# Nixie_HV_PSU_MAX1771.net
KiCad netlist of a schematic drawn in EAGLE
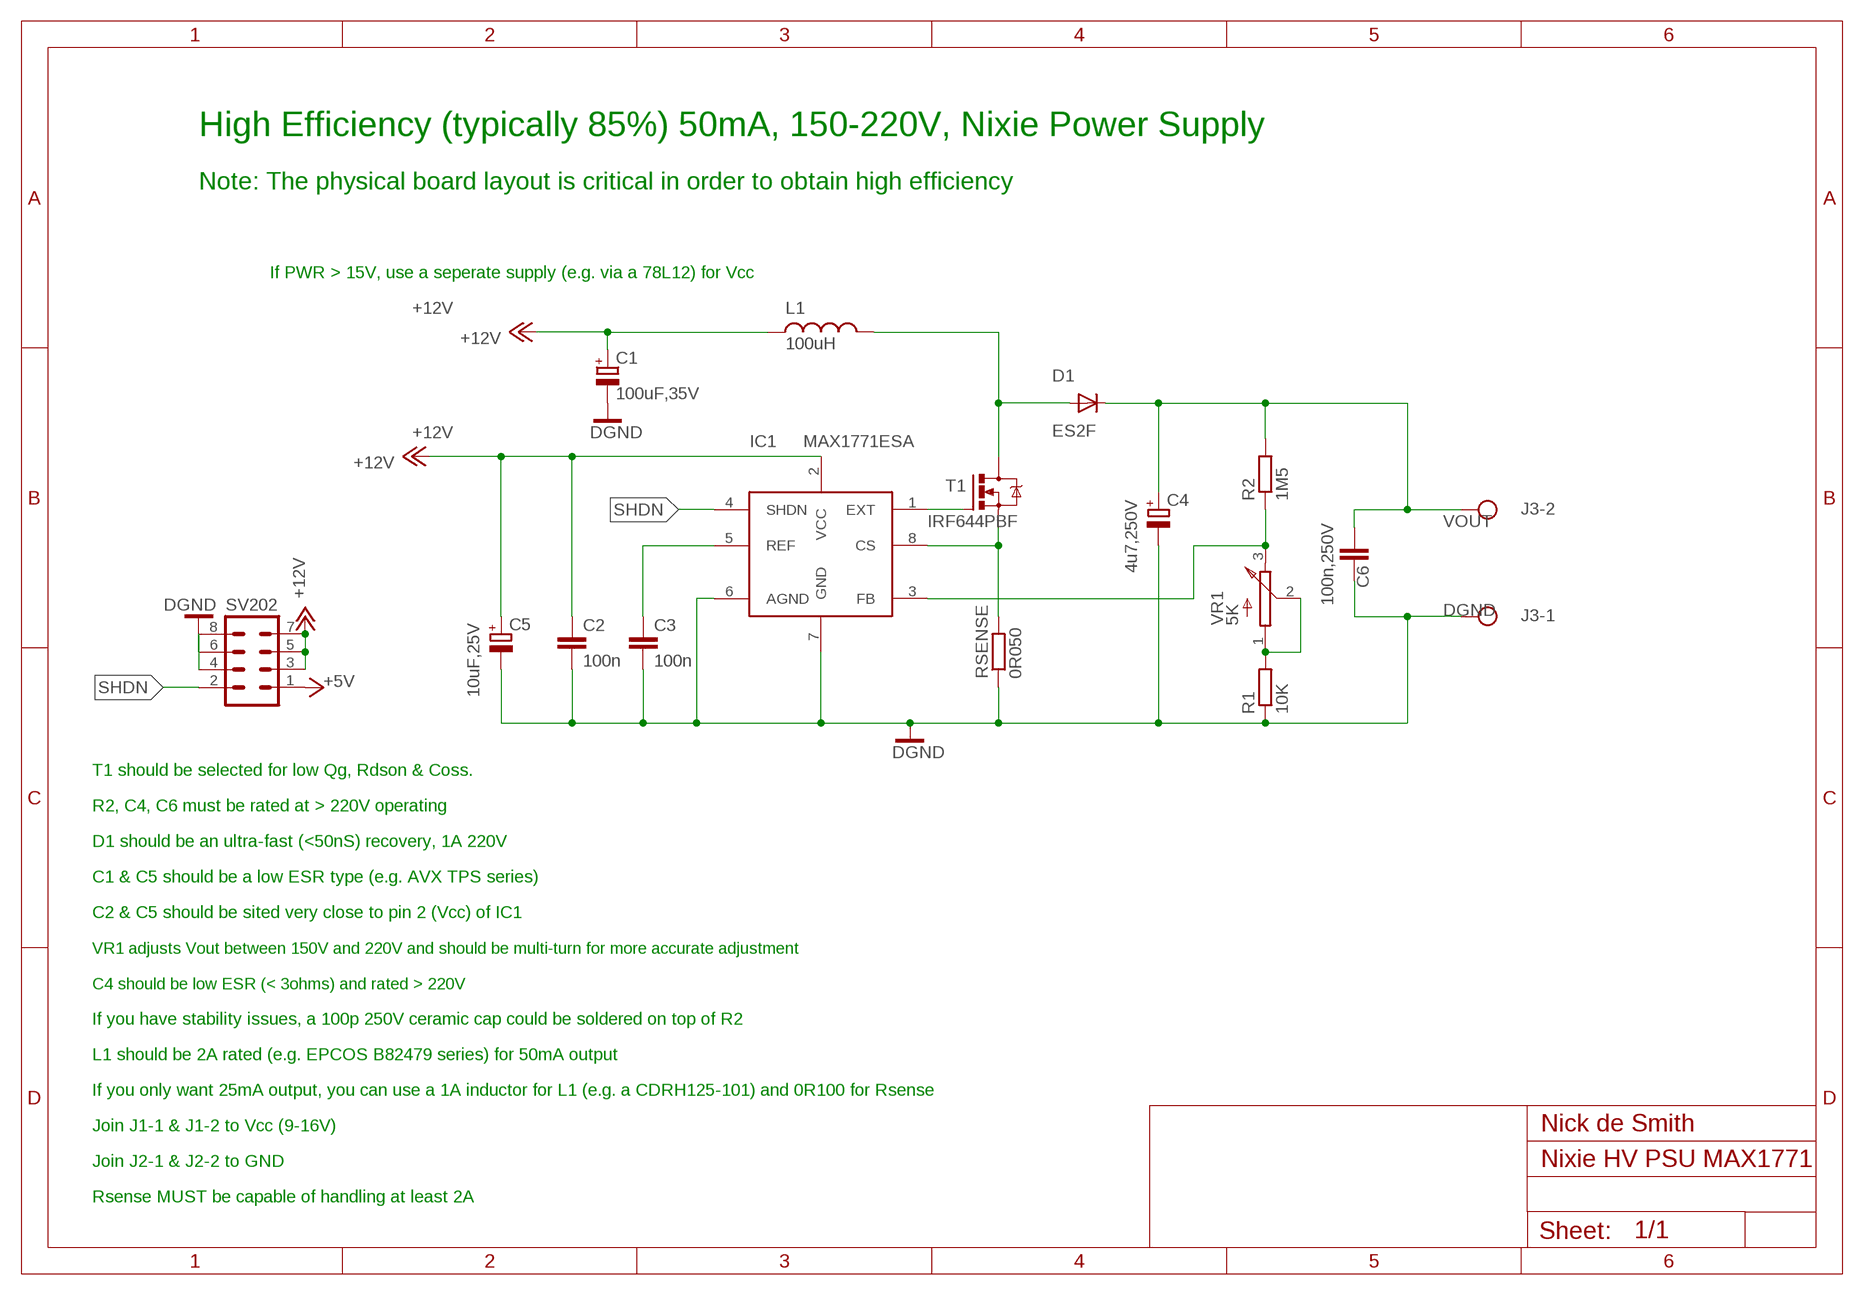
[diagram p0: schematic, sheet 1]

(export (version "E")
  (design (tool "Eeschema 10.0.6"))
  (components
    (comp (ref "C1")
      (value "100uF,35V")
      (footprint "eagle-import:C-EIA-7343")
      (libsource (lib "eagle-import") (part "C-POL-EU7343"))
    )
    (comp (ref "C2")
      (value "100n")
      (footprint "eagle-import:C0805")
      (libsource (lib "eagle-import") (part "C-EUC0805"))
    )
    (comp (ref "C3")
      (value "100n")
      (footprint "eagle-import:C0805")
      (libsource (lib "eagle-import") (part "C-EUC0805"))
    )
    (comp (ref "C4")
      (value "4u7,250V")
      (footprint "eagle-import:NICHICON-UJ-12")
      (libsource (lib "eagle-import") (part "C-POL-EU-NICHICON-UJ-12"))
    )
    (comp (ref "C5")
      (value "10uF,25V")
      (footprint "eagle-import:C-EIA-7343")
      (libsource (lib "eagle-import") (part "C-POL-EU7343"))
    )
    (comp (ref "C6")
      (value "100n,250V")
      (footprint "eagle-import:C2420")
      (libsource (lib "eagle-import") (part "C-EU-2420"))
    )
    (comp (ref "D1")
      (value "ES2F")
      (footprint "eagle-import:SMC")
      (libsource (lib "eagle-import") (part "DIODE-SMC"))
    )
    (comp (ref "IC1")
      (value "MAX1771ESA")
      (footprint "eagle-import:SO-8")
      (libsource (lib "eagle-import") (part "MAX1771ESA"))
    )
    (comp (ref "J3")
      (value "TERM-BLOCK-2-02IN")
      (footprint "eagle-import:SCREW-2-02")
      (libsource (lib "eagle-import") (part "TERM-BLOCK-2-02IN"))
    )
    (comp (ref "L1")
      (value "100uH")
      (footprint "eagle-import:L-B82479")
      (libsource (lib "eagle-import") (part "L-SMT-POWER-B82479"))
    )
    (comp (ref "R1")
      (value "10K")
      (footprint "eagle-import:R0805")
      (libsource (lib "eagle-import") (part "R-EU_R0805"))
    )
    (comp (ref "R2")
      (value "1M5")
      (footprint "eagle-import:R2512")
      (libsource (lib "eagle-import") (part "R-EU_R2512"))
    )
    (comp (ref "RSENSE")
      (value "0R050")
      (footprint "eagle-import:R2010")
      (libsource (lib "eagle-import") (part "R-EU_R2010"))
    )
    (comp (ref "SV202")
      (value "MA04-2")
      (footprint "eagle-import:MA04-2")
      (libsource (lib "eagle-import") (part "MA04-2"))
    )
    (comp (ref "T1")
      (value "IRF644PBF")
      (footprint "eagle-import:TO220BV")
      (libsource (lib "eagle-import") (part "IRF740"))
    )
    (comp (ref "VR1")
      (value "5K")
      (footprint "eagle-import:BOURNS-3214W")
      (libsource (lib "eagle-import") (part "TRIMPOT-3214W"))
    )
  )
  (nets
    (net (code "1") (name "+5V") (class "Default")
      (node (ref "SV202") (pin "1") (pinfunction "1_1") (pintype "passive"))
    )
    (net (code "2") (name "+12V") (class "Default")
      (node (ref "C1") (pin "+") (pinfunction "+_+") (pintype "passive"))
      (node (ref "C2") (pin "1") (pinfunction "1_1") (pintype "passive"))
      (node (ref "C5") (pin "+") (pinfunction "+_+") (pintype "passive"))
      (node (ref "IC1") (pin "2") (pinfunction "VCC_2") (pintype "input"))
      (node (ref "L1") (pin "P$1") (pinfunction "1_P$1") (pintype "passive"))
      (node (ref "SV202") (pin "3") (pinfunction "3_3") (pintype "passive"))
      (node (ref "SV202") (pin "5") (pinfunction "5_5") (pintype "passive"))
      (node (ref "SV202") (pin "7") (pinfunction "7_7") (pintype "passive"))
    )
    (net (code "3") (name "/VOUT") (class "Default")
      (node (ref "C4") (pin "2") (pinfunction "+_2") (pintype "passive"))
      (node (ref "C6") (pin "P$1") (pinfunction "1_P$1") (pintype "passive"))
      (node (ref "D1") (pin "C") (pinfunction "C_C") (pintype "passive"))
      (node (ref "J3") (pin "2") (pinfunction "P$1_2") (pintype "passive"))
      (node (ref "R2") (pin "2") (pinfunction "2_2") (pintype "passive"))
    )
    (net (code "4") (name "DGND") (class "Default")
      (node (ref "C1") (pin "-") (pinfunction "-_-") (pintype "passive"))
      (node (ref "C2") (pin "2") (pinfunction "2_2") (pintype "passive"))
      (node (ref "C3") (pin "2") (pinfunction "2_2") (pintype "passive"))
      (node (ref "C4") (pin "1") (pinfunction "-_1") (pintype "passive"))
      (node (ref "C5") (pin "-") (pinfunction "-_-") (pintype "passive"))
      (node (ref "C6") (pin "P$2") (pinfunction "2_P$2") (pintype "passive"))
      (node (ref "IC1") (pin "6") (pinfunction "AGND_6") (pintype "input"))
      (node (ref "IC1") (pin "7") (pinfunction "GND_7") (pintype "input"))
      (node (ref "J3") (pin "1") (pinfunction "P$1_1") (pintype "passive"))
      (node (ref "R1") (pin "1") (pinfunction "1_1") (pintype "passive"))
      (node (ref "RSENSE") (pin "1") (pinfunction "1_1") (pintype "passive"))
      (node (ref "SV202") (pin "4") (pinfunction "4_4") (pintype "passive"))
      (node (ref "SV202") (pin "6") (pinfunction "6_6") (pintype "passive"))
      (node (ref "SV202") (pin "8") (pinfunction "8_8") (pintype "passive"))
    )
    (net (code "5") (name "Net-(IC1-CS)") (class "Default")
      (node (ref "IC1") (pin "8") (pinfunction "CS_8") (pintype "input"))
      (node (ref "RSENSE") (pin "2") (pinfunction "2_2") (pintype "passive"))
      (node (ref "T1") (pin "S") (pinfunction "S_S") (pintype "passive"))
    )
    (net (code "6") (name "Net-(IC1-EXT)") (class "Default")
      (node (ref "IC1") (pin "1") (pinfunction "EXT_1") (pintype "output"))
      (node (ref "T1") (pin "G") (pinfunction "G_G") (pintype "passive"))
    )
    (net (code "7") (name "Net-(IC1-FB)") (class "Default")
      (node (ref "IC1") (pin "3") (pinfunction "FB_3") (pintype "input"))
      (node (ref "R2") (pin "1") (pinfunction "1_1") (pintype "passive"))
      (node (ref "VR1") (pin "3") (pinfunction "B_3") (pintype "passive"))
    )
    (net (code "8") (name "Net-(IC1-REF)") (class "Default")
      (node (ref "C3") (pin "1") (pinfunction "1_1") (pintype "passive"))
      (node (ref "IC1") (pin "5") (pinfunction "REF_5") (pintype "input"))
    )
    (net (code "9") (name "Net-(L1-2)") (class "Default")
      (node (ref "D1") (pin "A") (pinfunction "A_A") (pintype "passive"))
      (node (ref "L1") (pin "P$2") (pinfunction "2_P$2") (pintype "passive"))
      (node (ref "T1") (pin "D") (pinfunction "D_D") (pintype "passive"))
    )
    (net (code "10") (name "Net-(VR1-A)") (class "Default")
      (node (ref "R1") (pin "2") (pinfunction "2_2") (pintype "passive"))
      (node (ref "VR1") (pin "1") (pinfunction "A_1") (pintype "passive"))
      (node (ref "VR1") (pin "2") (pinfunction "W_2") (pintype "passive"))
    )
    (net (code "11") (name "SHDN") (class "Default")
      (node (ref "IC1") (pin "4") (pinfunction "SHDN_4") (pintype "input"))
      (node (ref "SV202") (pin "2") (pinfunction "2_2") (pintype "passive"))
    )
  )
)
